# PGTN021_octasource_controls.net
KiCad netlist of a schematic drawn in EAGLE
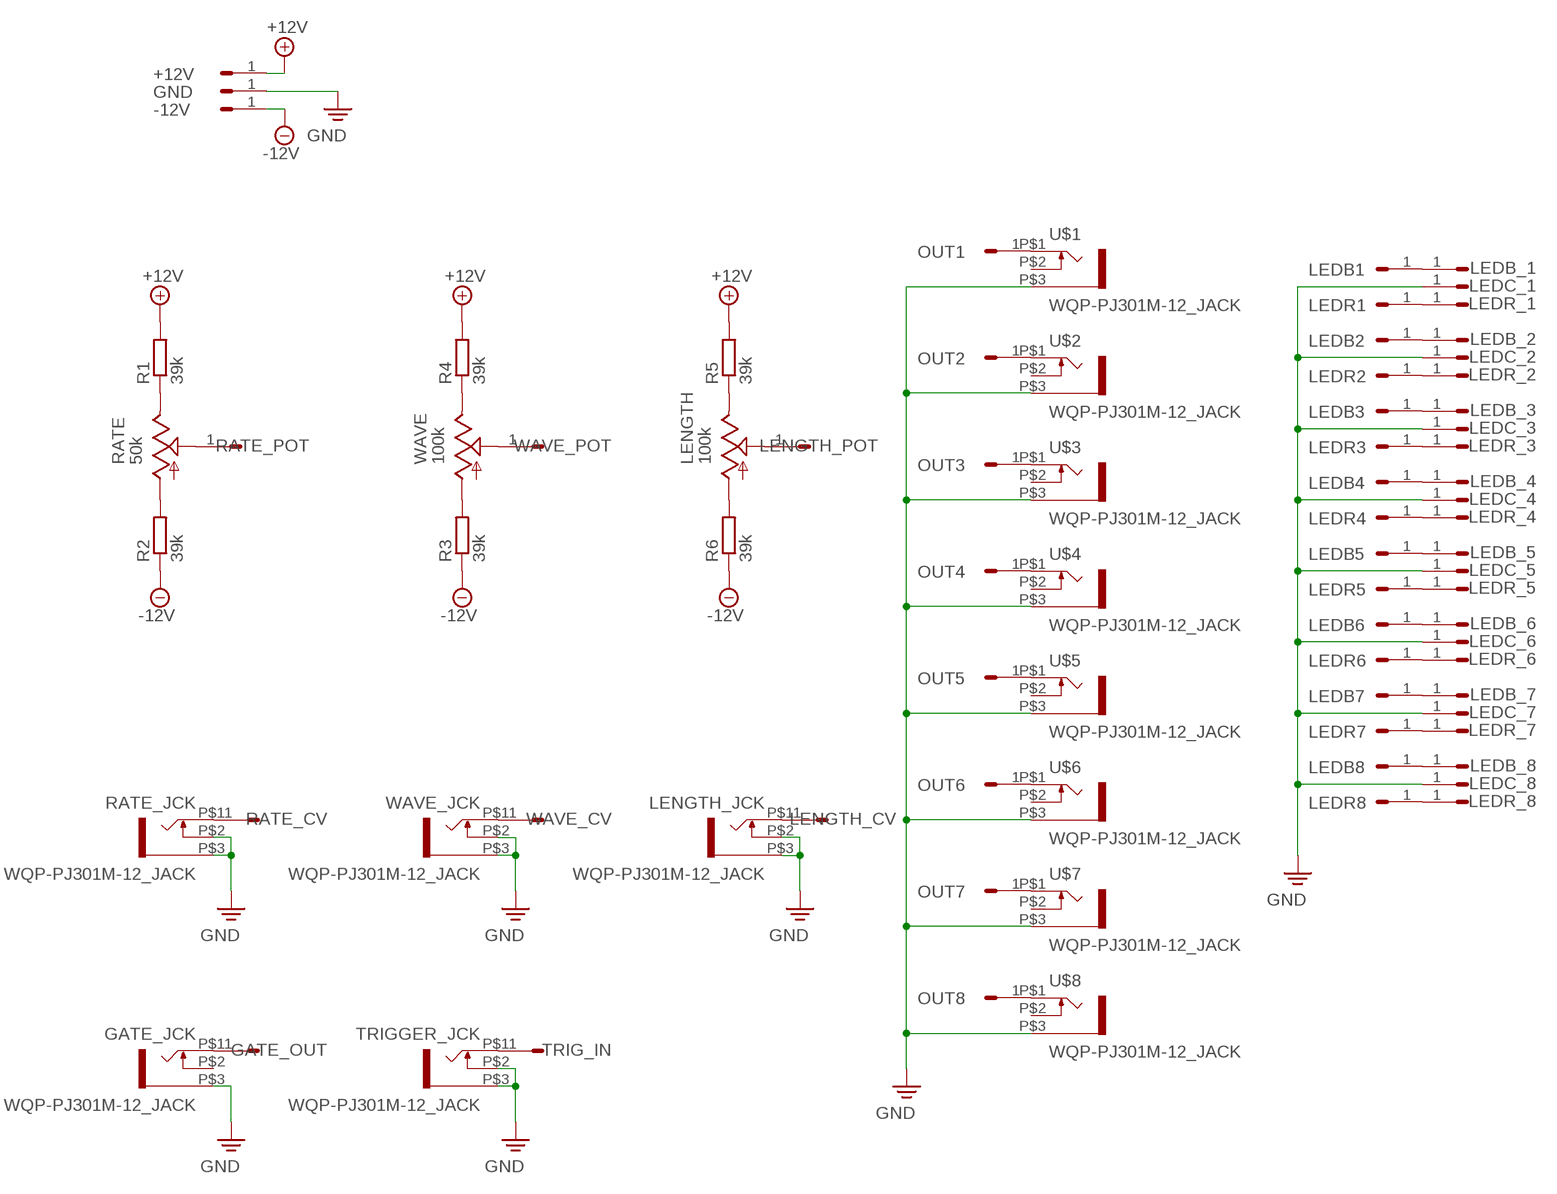
[diagram p0: schematic, sheet 1]

(export (version "E")
  (design (tool "Eeschema 10.0.6"))
  (components
    (comp (ref "+12V")
      (value "HEADER/MALE/01")
      (footprint "eagle-import:HEADER_MALE_01")
      (libsource (lib "eagle-import") (part "HEADER/MALE/01"))
    )
    (comp (ref "-12V")
      (value "HEADER/MALE/01")
      (footprint "eagle-import:HEADER_MALE_01")
      (libsource (lib "eagle-import") (part "HEADER/MALE/01"))
    )
    (comp (ref "GATE_JCK")
      (value "WQP-PJ301M-12_JACK")
      (footprint "eagle-import:WQP-PJ301M-12_JACK")
      (libsource (lib "eagle-import") (part "WQP-PJ301M-12_JACK"))
    )
    (comp (ref "GATE_OUT")
      (value "HEADER/MALE/01")
      (footprint "eagle-import:HEADER_MALE_01")
      (libsource (lib "eagle-import") (part "HEADER/MALE/01"))
    )
    (comp (ref "GND")
      (value "HEADER/MALE/01")
      (footprint "eagle-import:HEADER_MALE_01")
      (libsource (lib "eagle-import") (part "HEADER/MALE/01"))
    )
    (comp (ref "LEDB1")
      (value "HEADER/MALE/01")
      (footprint "eagle-import:HEADER_MALE_01")
      (libsource (lib "eagle-import") (part "HEADER/MALE/01"))
    )
    (comp (ref "LEDB2")
      (value "HEADER/MALE/01")
      (footprint "eagle-import:HEADER_MALE_01")
      (libsource (lib "eagle-import") (part "HEADER/MALE/01"))
    )
    (comp (ref "LEDB3")
      (value "HEADER/MALE/01")
      (footprint "eagle-import:HEADER_MALE_01")
      (libsource (lib "eagle-import") (part "HEADER/MALE/01"))
    )
    (comp (ref "LEDB4")
      (value "HEADER/MALE/01")
      (footprint "eagle-import:HEADER_MALE_01")
      (libsource (lib "eagle-import") (part "HEADER/MALE/01"))
    )
    (comp (ref "LEDB5")
      (value "HEADER/MALE/01")
      (footprint "eagle-import:HEADER_MALE_01")
      (libsource (lib "eagle-import") (part "HEADER/MALE/01"))
    )
    (comp (ref "LEDB6")
      (value "HEADER/MALE/01")
      (footprint "eagle-import:HEADER_MALE_01")
      (libsource (lib "eagle-import") (part "HEADER/MALE/01"))
    )
    (comp (ref "LEDB7")
      (value "HEADER/MALE/01")
      (footprint "eagle-import:HEADER_MALE_01")
      (libsource (lib "eagle-import") (part "HEADER/MALE/01"))
    )
    (comp (ref "LEDB8")
      (value "HEADER/MALE/01")
      (footprint "eagle-import:HEADER_MALE_01")
      (libsource (lib "eagle-import") (part "HEADER/MALE/01"))
    )
    (comp (ref "LEDB_1")
      (value "HEADER/MALE/01")
      (footprint "eagle-import:HEADER_MALE_01")
      (libsource (lib "eagle-import") (part "HEADER/MALE/01"))
    )
    (comp (ref "LEDB_2")
      (value "HEADER/MALE/01")
      (footprint "eagle-import:HEADER_MALE_01")
      (libsource (lib "eagle-import") (part "HEADER/MALE/01"))
    )
    (comp (ref "LEDB_3")
      (value "HEADER/MALE/01")
      (footprint "eagle-import:HEADER_MALE_01")
      (libsource (lib "eagle-import") (part "HEADER/MALE/01"))
    )
    (comp (ref "LEDB_4")
      (value "HEADER/MALE/01")
      (footprint "eagle-import:HEADER_MALE_01")
      (libsource (lib "eagle-import") (part "HEADER/MALE/01"))
    )
    (comp (ref "LEDB_5")
      (value "HEADER/MALE/01")
      (footprint "eagle-import:HEADER_MALE_01")
      (libsource (lib "eagle-import") (part "HEADER/MALE/01"))
    )
    (comp (ref "LEDB_6")
      (value "HEADER/MALE/01")
      (footprint "eagle-import:HEADER_MALE_01")
      (libsource (lib "eagle-import") (part "HEADER/MALE/01"))
    )
    (comp (ref "LEDB_7")
      (value "HEADER/MALE/01")
      (footprint "eagle-import:HEADER_MALE_01")
      (libsource (lib "eagle-import") (part "HEADER/MALE/01"))
    )
    (comp (ref "LEDB_8")
      (value "HEADER/MALE/01")
      (footprint "eagle-import:HEADER_MALE_01")
      (libsource (lib "eagle-import") (part "HEADER/MALE/01"))
    )
    (comp (ref "LEDC_1")
      (value "HEADER/MALE/01")
      (footprint "eagle-import:HEADER_MALE_01")
      (libsource (lib "eagle-import") (part "HEADER/MALE/01"))
    )
    (comp (ref "LEDC_2")
      (value "HEADER/MALE/01")
      (footprint "eagle-import:HEADER_MALE_01")
      (libsource (lib "eagle-import") (part "HEADER/MALE/01"))
    )
    (comp (ref "LEDC_3")
      (value "HEADER/MALE/01")
      (footprint "eagle-import:HEADER_MALE_01")
      (libsource (lib "eagle-import") (part "HEADER/MALE/01"))
    )
    (comp (ref "LEDC_4")
      (value "HEADER/MALE/01")
      (footprint "eagle-import:HEADER_MALE_01")
      (libsource (lib "eagle-import") (part "HEADER/MALE/01"))
    )
    (comp (ref "LEDC_5")
      (value "HEADER/MALE/01")
      (footprint "eagle-import:HEADER_MALE_01")
      (libsource (lib "eagle-import") (part "HEADER/MALE/01"))
    )
    (comp (ref "LEDC_6")
      (value "HEADER/MALE/01")
      (footprint "eagle-import:HEADER_MALE_01")
      (libsource (lib "eagle-import") (part "HEADER/MALE/01"))
    )
    (comp (ref "LEDC_7")
      (value "HEADER/MALE/01")
      (footprint "eagle-import:HEADER_MALE_01")
      (libsource (lib "eagle-import") (part "HEADER/MALE/01"))
    )
    (comp (ref "LEDC_8")
      (value "HEADER/MALE/01")
      (footprint "eagle-import:HEADER_MALE_01")
      (libsource (lib "eagle-import") (part "HEADER/MALE/01"))
    )
    (comp (ref "LEDR1")
      (value "HEADER/MALE/01")
      (footprint "eagle-import:HEADER_MALE_01")
      (libsource (lib "eagle-import") (part "HEADER/MALE/01"))
    )
    (comp (ref "LEDR2")
      (value "HEADER/MALE/01")
      (footprint "eagle-import:HEADER_MALE_01")
      (libsource (lib "eagle-import") (part "HEADER/MALE/01"))
    )
    (comp (ref "LEDR3")
      (value "HEADER/MALE/01")
      (footprint "eagle-import:HEADER_MALE_01")
      (libsource (lib "eagle-import") (part "HEADER/MALE/01"))
    )
    (comp (ref "LEDR4")
      (value "HEADER/MALE/01")
      (footprint "eagle-import:HEADER_MALE_01")
      (libsource (lib "eagle-import") (part "HEADER/MALE/01"))
    )
    (comp (ref "LEDR5")
      (value "HEADER/MALE/01")
      (footprint "eagle-import:HEADER_MALE_01")
      (libsource (lib "eagle-import") (part "HEADER/MALE/01"))
    )
    (comp (ref "LEDR6")
      (value "HEADER/MALE/01")
      (footprint "eagle-import:HEADER_MALE_01")
      (libsource (lib "eagle-import") (part "HEADER/MALE/01"))
    )
    (comp (ref "LEDR7")
      (value "HEADER/MALE/01")
      (footprint "eagle-import:HEADER_MALE_01")
      (libsource (lib "eagle-import") (part "HEADER/MALE/01"))
    )
    (comp (ref "LEDR8")
      (value "HEADER/MALE/01")
      (footprint "eagle-import:HEADER_MALE_01")
      (libsource (lib "eagle-import") (part "HEADER/MALE/01"))
    )
    (comp (ref "LEDR_1")
      (value "HEADER/MALE/01")
      (footprint "eagle-import:HEADER_MALE_01")
      (libsource (lib "eagle-import") (part "HEADER/MALE/01"))
    )
    (comp (ref "LEDR_2")
      (value "HEADER/MALE/01")
      (footprint "eagle-import:HEADER_MALE_01")
      (libsource (lib "eagle-import") (part "HEADER/MALE/01"))
    )
    (comp (ref "LEDR_3")
      (value "HEADER/MALE/01")
      (footprint "eagle-import:HEADER_MALE_01")
      (libsource (lib "eagle-import") (part "HEADER/MALE/01"))
    )
    (comp (ref "LEDR_4")
      (value "HEADER/MALE/01")
      (footprint "eagle-import:HEADER_MALE_01")
      (libsource (lib "eagle-import") (part "HEADER/MALE/01"))
    )
    (comp (ref "LEDR_5")
      (value "HEADER/MALE/01")
      (footprint "eagle-import:HEADER_MALE_01")
      (libsource (lib "eagle-import") (part "HEADER/MALE/01"))
    )
    (comp (ref "LEDR_6")
      (value "HEADER/MALE/01")
      (footprint "eagle-import:HEADER_MALE_01")
      (libsource (lib "eagle-import") (part "HEADER/MALE/01"))
    )
    (comp (ref "LEDR_7")
      (value "HEADER/MALE/01")
      (footprint "eagle-import:HEADER_MALE_01")
      (libsource (lib "eagle-import") (part "HEADER/MALE/01"))
    )
    (comp (ref "LEDR_8")
      (value "HEADER/MALE/01")
      (footprint "eagle-import:HEADER_MALE_01")
      (libsource (lib "eagle-import") (part "HEADER/MALE/01"))
    )
    (comp (ref "LENGTH")
      (value "100k")
      (footprint "eagle-import:9MM_SNAP-IN_POT")
      (libsource (lib "eagle-import") (part "9MM_SNAP-IN_POT_"))
    )
    (comp (ref "LENGTH_CV")
      (value "HEADER/MALE/01")
      (footprint "eagle-import:HEADER_MALE_01")
      (libsource (lib "eagle-import") (part "HEADER/MALE/01"))
    )
    (comp (ref "LENGTH_JCK")
      (value "WQP-PJ301M-12_JACK")
      (footprint "eagle-import:WQP-PJ301M-12_JACK")
      (libsource (lib "eagle-import") (part "WQP-PJ301M-12_JACK"))
    )
    (comp (ref "LENGTH_POT")
      (value "HEADER/MALE/01")
      (footprint "eagle-import:HEADER_MALE_01")
      (libsource (lib "eagle-import") (part "HEADER/MALE/01"))
    )
    (comp (ref "OUT1")
      (value "HEADER/MALE/01")
      (footprint "eagle-import:HEADER_MALE_01")
      (libsource (lib "eagle-import") (part "HEADER/MALE/01"))
    )
    (comp (ref "OUT2")
      (value "HEADER/MALE/01")
      (footprint "eagle-import:HEADER_MALE_01")
      (libsource (lib "eagle-import") (part "HEADER/MALE/01"))
    )
    (comp (ref "OUT3")
      (value "HEADER/MALE/01")
      (footprint "eagle-import:HEADER_MALE_01")
      (libsource (lib "eagle-import") (part "HEADER/MALE/01"))
    )
    (comp (ref "OUT4")
      (value "HEADER/MALE/01")
      (footprint "eagle-import:HEADER_MALE_01")
      (libsource (lib "eagle-import") (part "HEADER/MALE/01"))
    )
    (comp (ref "OUT5")
      (value "HEADER/MALE/01")
      (footprint "eagle-import:HEADER_MALE_01")
      (libsource (lib "eagle-import") (part "HEADER/MALE/01"))
    )
    (comp (ref "OUT6")
      (value "HEADER/MALE/01")
      (footprint "eagle-import:HEADER_MALE_01")
      (libsource (lib "eagle-import") (part "HEADER/MALE/01"))
    )
    (comp (ref "OUT7")
      (value "HEADER/MALE/01")
      (footprint "eagle-import:HEADER_MALE_01")
      (libsource (lib "eagle-import") (part "HEADER/MALE/01"))
    )
    (comp (ref "OUT8")
      (value "HEADER/MALE/01")
      (footprint "eagle-import:HEADER_MALE_01")
      (libsource (lib "eagle-import") (part "HEADER/MALE/01"))
    )
    (comp (ref "R1")
      (value "39k")
      (footprint "eagle-import:RESISTOR_7.5")
      (libsource (lib "eagle-import") (part "RESISTORRESISTOR/UPRIGHT/7.5"))
    )
    (comp (ref "R2")
      (value "39k")
      (footprint "eagle-import:RESISTOR_7.5")
      (libsource (lib "eagle-import") (part "RESISTORRESISTOR/UPRIGHT/7.5"))
    )
    (comp (ref "R3")
      (value "39k")
      (footprint "eagle-import:RESISTOR_7.5")
      (libsource (lib "eagle-import") (part "RESISTORRESISTOR/UPRIGHT/7.5"))
    )
    (comp (ref "R4")
      (value "39k")
      (footprint "eagle-import:RESISTOR_7.5")
      (libsource (lib "eagle-import") (part "RESISTORRESISTOR/UPRIGHT/7.5"))
    )
    (comp (ref "R5")
      (value "39k")
      (footprint "eagle-import:RESISTOR_7.5")
      (libsource (lib "eagle-import") (part "RESISTORRESISTOR/UPRIGHT/7.5"))
    )
    (comp (ref "R6")
      (value "39k")
      (footprint "eagle-import:RESISTOR_7.5")
      (libsource (lib "eagle-import") (part "RESISTORRESISTOR/UPRIGHT/7.5"))
    )
    (comp (ref "RATE")
      (value "50k")
      (footprint "eagle-import:9MM_SNAP-IN_POT")
      (libsource (lib "eagle-import") (part "9MM_SNAP-IN_POT_"))
    )
    (comp (ref "RATE_CV")
      (value "HEADER/MALE/01")
      (footprint "eagle-import:HEADER_MALE_01")
      (libsource (lib "eagle-import") (part "HEADER/MALE/01"))
    )
    (comp (ref "RATE_JCK")
      (value "WQP-PJ301M-12_JACK")
      (footprint "eagle-import:WQP-PJ301M-12_JACK")
      (libsource (lib "eagle-import") (part "WQP-PJ301M-12_JACK"))
    )
    (comp (ref "RATE_POT")
      (value "HEADER/MALE/01")
      (footprint "eagle-import:HEADER_MALE_01")
      (libsource (lib "eagle-import") (part "HEADER/MALE/01"))
    )
    (comp (ref "TRIGGER_JCK")
      (value "WQP-PJ301M-12_JACK")
      (footprint "eagle-import:WQP-PJ301M-12_JACK")
      (libsource (lib "eagle-import") (part "WQP-PJ301M-12_JACK"))
    )
    (comp (ref "TRIG_IN")
      (value "HEADER/MALE/01")
      (footprint "eagle-import:HEADER_MALE_01")
      (libsource (lib "eagle-import") (part "HEADER/MALE/01"))
    )
    (comp (ref "U$1")
      (value "WQP-PJ301M-12_JACK")
      (footprint "eagle-import:WQP-PJ301M-12_JACK")
      (libsource (lib "eagle-import") (part "WQP-PJ301M-12_JACK"))
    )
    (comp (ref "U$2")
      (value "WQP-PJ301M-12_JACK")
      (footprint "eagle-import:WQP-PJ301M-12_JACK")
      (libsource (lib "eagle-import") (part "WQP-PJ301M-12_JACK"))
    )
    (comp (ref "U$3")
      (value "WQP-PJ301M-12_JACK")
      (footprint "eagle-import:WQP-PJ301M-12_JACK")
      (libsource (lib "eagle-import") (part "WQP-PJ301M-12_JACK"))
    )
    (comp (ref "U$4")
      (value "WQP-PJ301M-12_JACK")
      (footprint "eagle-import:WQP-PJ301M-12_JACK")
      (libsource (lib "eagle-import") (part "WQP-PJ301M-12_JACK"))
    )
    (comp (ref "U$5")
      (value "WQP-PJ301M-12_JACK")
      (footprint "eagle-import:WQP-PJ301M-12_JACK")
      (libsource (lib "eagle-import") (part "WQP-PJ301M-12_JACK"))
    )
    (comp (ref "U$6")
      (value "WQP-PJ301M-12_JACK")
      (footprint "eagle-import:WQP-PJ301M-12_JACK")
      (libsource (lib "eagle-import") (part "WQP-PJ301M-12_JACK"))
    )
    (comp (ref "U$7")
      (value "WQP-PJ301M-12_JACK")
      (footprint "eagle-import:WQP-PJ301M-12_JACK")
      (libsource (lib "eagle-import") (part "WQP-PJ301M-12_JACK"))
    )
    (comp (ref "U$8")
      (value "WQP-PJ301M-12_JACK")
      (footprint "eagle-import:WQP-PJ301M-12_JACK")
      (libsource (lib "eagle-import") (part "WQP-PJ301M-12_JACK"))
    )
    (comp (ref "WAVE")
      (value "100k")
      (footprint "eagle-import:9MM_SNAP-IN_POT")
      (libsource (lib "eagle-import") (part "9MM_SNAP-IN_POT_"))
    )
    (comp (ref "WAVE_CV")
      (value "HEADER/MALE/01")
      (footprint "eagle-import:HEADER_MALE_01")
      (libsource (lib "eagle-import") (part "HEADER/MALE/01"))
    )
    (comp (ref "WAVE_JCK")
      (value "WQP-PJ301M-12_JACK")
      (footprint "eagle-import:WQP-PJ301M-12_JACK")
      (libsource (lib "eagle-import") (part "WQP-PJ301M-12_JACK"))
    )
    (comp (ref "WAVE_POT")
      (value "HEADER/MALE/01")
      (footprint "eagle-import:HEADER_MALE_01")
      (libsource (lib "eagle-import") (part "HEADER/MALE/01"))
    )
  )
  (nets
    (net (code "1") (name "+12V") (class "Default")
      (node (ref "+12V") (pin "1") (pinfunction "3_1") (pintype "passive"))
      (node (ref "R1") (pin "2") (pinfunction "2_2") (pintype "passive"))
      (node (ref "R4") (pin "2") (pinfunction "2_2") (pintype "passive"))
      (node (ref "R5") (pin "2") (pinfunction "2_2") (pintype "passive"))
    )
    (net (code "2") (name "-12V") (class "Default")
      (node (ref "-12V") (pin "1") (pinfunction "3_1") (pintype "passive"))
      (node (ref "R2") (pin "1") (pinfunction "1_1") (pintype "passive"))
      (node (ref "R3") (pin "1") (pinfunction "1_1") (pintype "passive"))
      (node (ref "R6") (pin "1") (pinfunction "1_1") (pintype "passive"))
    )
    (net (code "3") (name "GND") (class "Default")
      (node (ref "GATE_JCK") (pin "P$3") (pinfunction "1_P$3") (pintype "passive"))
      (node (ref "GND") (pin "1") (pinfunction "3_1") (pintype "passive"))
      (node (ref "LEDC_1") (pin "1") (pinfunction "3_1") (pintype "passive"))
      (node (ref "LEDC_2") (pin "1") (pinfunction "3_1") (pintype "passive"))
      (node (ref "LEDC_3") (pin "1") (pinfunction "3_1") (pintype "passive"))
      (node (ref "LEDC_4") (pin "1") (pinfunction "3_1") (pintype "passive"))
      (node (ref "LEDC_5") (pin "1") (pinfunction "3_1") (pintype "passive"))
      (node (ref "LEDC_6") (pin "1") (pinfunction "3_1") (pintype "passive"))
      (node (ref "LEDC_7") (pin "1") (pinfunction "3_1") (pintype "passive"))
      (node (ref "LEDC_8") (pin "1") (pinfunction "3_1") (pintype "passive"))
      (node (ref "LENGTH_JCK") (pin "P$2") (pinfunction "3_P$2") (pintype "passive"))
      (node (ref "LENGTH_JCK") (pin "P$3") (pinfunction "1_P$3") (pintype "passive"))
      (node (ref "RATE_JCK") (pin "P$2") (pinfunction "3_P$2") (pintype "passive"))
      (node (ref "RATE_JCK") (pin "P$3") (pinfunction "1_P$3") (pintype "passive"))
      (node (ref "TRIGGER_JCK") (pin "P$2") (pinfunction "3_P$2") (pintype "passive"))
      (node (ref "TRIGGER_JCK") (pin "P$3") (pinfunction "1_P$3") (pintype "passive"))
      (node (ref "U$1") (pin "P$3") (pinfunction "1_P$3") (pintype "passive"))
      (node (ref "U$2") (pin "P$3") (pinfunction "1_P$3") (pintype "passive"))
      (node (ref "U$3") (pin "P$3") (pinfunction "1_P$3") (pintype "passive"))
      (node (ref "U$4") (pin "P$3") (pinfunction "1_P$3") (pintype "passive"))
      (node (ref "U$5") (pin "P$3") (pinfunction "1_P$3") (pintype "passive"))
      (node (ref "U$6") (pin "P$3") (pinfunction "1_P$3") (pintype "passive"))
      (node (ref "U$7") (pin "P$3") (pinfunction "1_P$3") (pintype "passive"))
      (node (ref "U$8") (pin "P$3") (pinfunction "1_P$3") (pintype "passive"))
      (node (ref "WAVE_JCK") (pin "P$2") (pinfunction "3_P$2") (pintype "passive"))
      (node (ref "WAVE_JCK") (pin "P$3") (pinfunction "1_P$3") (pintype "passive"))
    )
    (net (code "4") (name "Net-(GATE_JCK-2)") (class "Default")
      (node (ref "GATE_JCK") (pin "P$1") (pinfunction "2_P$1") (pintype "passive"))
      (node (ref "GATE_OUT") (pin "1") (pinfunction "3_1") (pintype "passive"))
    )
    (net (code "5") (name "Net-(LEDB1-3)") (class "Default")
      (node (ref "LEDB1") (pin "1") (pinfunction "3_1") (pintype "passive"))
      (node (ref "LEDB_1") (pin "1") (pinfunction "3_1") (pintype "passive"))
    )
    (net (code "6") (name "Net-(LEDB2-3)") (class "Default")
      (node (ref "LEDB2") (pin "1") (pinfunction "3_1") (pintype "passive"))
      (node (ref "LEDB_2") (pin "1") (pinfunction "3_1") (pintype "passive"))
    )
    (net (code "7") (name "Net-(LEDB3-3)") (class "Default")
      (node (ref "LEDB3") (pin "1") (pinfunction "3_1") (pintype "passive"))
      (node (ref "LEDB_3") (pin "1") (pinfunction "3_1") (pintype "passive"))
    )
    (net (code "8") (name "Net-(LEDB4-3)") (class "Default")
      (node (ref "LEDB4") (pin "1") (pinfunction "3_1") (pintype "passive"))
      (node (ref "LEDB_4") (pin "1") (pinfunction "3_1") (pintype "passive"))
    )
    (net (code "9") (name "Net-(LEDB5-3)") (class "Default")
      (node (ref "LEDB5") (pin "1") (pinfunction "3_1") (pintype "passive"))
      (node (ref "LEDB_5") (pin "1") (pinfunction "3_1") (pintype "passive"))
    )
    (net (code "10") (name "Net-(LEDB6-3)") (class "Default")
      (node (ref "LEDB6") (pin "1") (pinfunction "3_1") (pintype "passive"))
      (node (ref "LEDB_6") (pin "1") (pinfunction "3_1") (pintype "passive"))
    )
    (net (code "11") (name "Net-(LEDB7-3)") (class "Default")
      (node (ref "LEDB7") (pin "1") (pinfunction "3_1") (pintype "passive"))
      (node (ref "LEDB_7") (pin "1") (pinfunction "3_1") (pintype "passive"))
    )
    (net (code "12") (name "Net-(LEDB8-3)") (class "Default")
      (node (ref "LEDB8") (pin "1") (pinfunction "3_1") (pintype "passive"))
      (node (ref "LEDB_8") (pin "1") (pinfunction "3_1") (pintype "passive"))
    )
    (net (code "13") (name "Net-(LEDR1-3)") (class "Default")
      (node (ref "LEDR1") (pin "1") (pinfunction "3_1") (pintype "passive"))
      (node (ref "LEDR_1") (pin "1") (pinfunction "3_1") (pintype "passive"))
    )
    (net (code "14") (name "Net-(LEDR2-3)") (class "Default")
      (node (ref "LEDR2") (pin "1") (pinfunction "3_1") (pintype "passive"))
      (node (ref "LEDR_2") (pin "1") (pinfunction "3_1") (pintype "passive"))
    )
    (net (code "15") (name "Net-(LEDR3-3)") (class "Default")
      (node (ref "LEDR3") (pin "1") (pinfunction "3_1") (pintype "passive"))
      (node (ref "LEDR_3") (pin "1") (pinfunction "3_1") (pintype "passive"))
    )
    (net (code "16") (name "Net-(LEDR4-3)") (class "Default")
      (node (ref "LEDR4") (pin "1") (pinfunction "3_1") (pintype "passive"))
      (node (ref "LEDR_4") (pin "1") (pinfunction "3_1") (pintype "passive"))
    )
    (net (code "17") (name "Net-(LEDR5-3)") (class "Default")
      (node (ref "LEDR5") (pin "1") (pinfunction "3_1") (pintype "passive"))
      (node (ref "LEDR_5") (pin "1") (pinfunction "3_1") (pintype "passive"))
    )
    (net (code "18") (name "Net-(LEDR6-3)") (class "Default")
      (node (ref "LEDR6") (pin "1") (pinfunction "3_1") (pintype "passive"))
      (node (ref "LEDR_6") (pin "1") (pinfunction "3_1") (pintype "passive"))
    )
    (net (code "19") (name "Net-(LEDR7-3)") (class "Default")
      (node (ref "LEDR7") (pin "1") (pinfunction "3_1") (pintype "passive"))
      (node (ref "LEDR_7") (pin "1") (pinfunction "3_1") (pintype "passive"))
    )
    (net (code "20") (name "Net-(LEDR8-3)") (class "Default")
      (node (ref "LEDR8") (pin "1") (pinfunction "3_1") (pintype "passive"))
      (node (ref "LEDR_8") (pin "1") (pinfunction "3_1") (pintype "passive"))
    )
    (net (code "21") (name "Net-(LENGTH-A)") (class "Default")
      (node (ref "LENGTH") (pin "1") (pinfunction "A_1") (pintype "passive"))
      (node (ref "R6") (pin "2") (pinfunction "2_2") (pintype "passive"))
    )
    (net (code "22") (name "Net-(LENGTH-E)") (class "Default")
      (node (ref "LENGTH") (pin "3") (pinfunction "E_3") (pintype "passive"))
      (node (ref "R5") (pin "1") (pinfunction "1_1") (pintype "passive"))
    )
    (net (code "23") (name "Net-(LENGTH-S)") (class "Default")
      (node (ref "LENGTH") (pin "2") (pinfunction "S_2") (pintype "passive"))
      (node (ref "LENGTH_POT") (pin "1") (pinfunction "3_1") (pintype "passive"))
    )
    (net (code "24") (name "Net-(LENGTH_CV-3)") (class "Default")
      (node (ref "LENGTH_CV") (pin "1") (pinfunction "3_1") (pintype "passive"))
      (node (ref "LENGTH_JCK") (pin "P$1") (pinfunction "2_P$1") (pintype "passive"))
    )
    (net (code "25") (name "Net-(OUT1-3)") (class "Default")
      (node (ref "OUT1") (pin "1") (pinfunction "3_1") (pintype "passive"))
      (node (ref "U$1") (pin "P$1") (pinfunction "2_P$1") (pintype "passive"))
    )
    (net (code "26") (name "Net-(OUT2-3)") (class "Default")
      (node (ref "OUT2") (pin "1") (pinfunction "3_1") (pintype "passive"))
      (node (ref "U$2") (pin "P$1") (pinfunction "2_P$1") (pintype "passive"))
    )
    (net (code "27") (name "Net-(OUT3-3)") (class "Default")
      (node (ref "OUT3") (pin "1") (pinfunction "3_1") (pintype "passive"))
      (node (ref "U$3") (pin "P$1") (pinfunction "2_P$1") (pintype "passive"))
    )
    (net (code "28") (name "Net-(OUT4-3)") (class "Default")
      (node (ref "OUT4") (pin "1") (pinfunction "3_1") (pintype "passive"))
      (node (ref "U$4") (pin "P$1") (pinfunction "2_P$1") (pintype "passive"))
    )
    (net (code "29") (name "Net-(OUT5-3)") (class "Default")
      (node (ref "OUT5") (pin "1") (pinfunction "3_1") (pintype "passive"))
      (node (ref "U$5") (pin "P$1") (pinfunction "2_P$1") (pintype "passive"))
    )
    (net (code "30") (name "Net-(OUT6-3)") (class "Default")
      (node (ref "OUT6") (pin "1") (pinfunction "3_1") (pintype "passive"))
      (node (ref "U$6") (pin "P$1") (pinfunction "2_P$1") (pintype "passive"))
    )
    (net (code "31") (name "Net-(OUT7-3)") (class "Default")
      (node (ref "OUT7") (pin "1") (pinfunction "3_1") (pintype "passive"))
      (node (ref "U$7") (pin "P$1") (pinfunction "2_P$1") (pintype "passive"))
    )
    (net (code "32") (name "Net-(OUT8-3)") (class "Default")
      (node (ref "OUT8") (pin "1") (pinfunction "3_1") (pintype "passive"))
      (node (ref "U$8") (pin "P$1") (pinfunction "2_P$1") (pintype "passive"))
    )
    (net (code "33") (name "Net-(RATE-A)") (class "Default")
      (node (ref "R2") (pin "2") (pinfunction "2_2") (pintype "passive"))
      (node (ref "RATE") (pin "1") (pinfunction "A_1") (pintype "passive"))
    )
    (net (code "34") (name "Net-(RATE-E)") (class "Default")
      (node (ref "R1") (pin "1") (pinfunction "1_1") (pintype "passive"))
      (node (ref "RATE") (pin "3") (pinfunction "E_3") (pintype "passive"))
    )
    (net (code "35") (name "Net-(RATE-S)") (class "Default")
      (node (ref "RATE") (pin "2") (pinfunction "S_2") (pintype "passive"))
      (node (ref "RATE_POT") (pin "1") (pinfunction "3_1") (pintype "passive"))
    )
    (net (code "36") (name "Net-(RATE_CV-3)") (class "Default")
      (node (ref "RATE_CV") (pin "1") (pinfunction "3_1") (pintype "passive"))
      (node (ref "RATE_JCK") (pin "P$1") (pinfunction "2_P$1") (pintype "passive"))
    )
    (net (code "37") (name "Net-(TRIGGER_JCK-2)") (class "Default")
      (node (ref "TRIGGER_JCK") (pin "P$1") (pinfunction "2_P$1") (pintype "passive"))
      (node (ref "TRIG_IN") (pin "1") (pinfunction "3_1") (pintype "passive"))
    )
    (net (code "38") (name "Net-(WAVE-A)") (class "Default")
      (node (ref "R3") (pin "2") (pinfunction "2_2") (pintype "passive"))
      (node (ref "WAVE") (pin "1") (pinfunction "A_1") (pintype "passive"))
    )
    (net (code "39") (name "Net-(WAVE-E)") (class "Default")
      (node (ref "R4") (pin "1") (pinfunction "1_1") (pintype "passive"))
      (node (ref "WAVE") (pin "3") (pinfunction "E_3") (pintype "passive"))
    )
    (net (code "40") (name "Net-(WAVE-S)") (class "Default")
      (node (ref "WAVE") (pin "2") (pinfunction "S_2") (pintype "passive"))
      (node (ref "WAVE_POT") (pin "1") (pinfunction "3_1") (pintype "passive"))
    )
    (net (code "41") (name "Net-(WAVE_CV-3)") (class "Default")
      (node (ref "WAVE_CV") (pin "1") (pinfunction "3_1") (pintype "passive"))
      (node (ref "WAVE_JCK") (pin "P$1") (pinfunction "2_P$1") (pintype "passive"))
    )
    (net (code "42") (name "unconnected-(GATE_JCK-3-PadP$2)") (class "Default")
      (node (ref "GATE_JCK") (pin "P$2") (pinfunction "3_P$2") (pintype "passive"))
    )
    (net (code "43") (name "unconnected-(U$1-3-PadP$2)") (class "Default")
      (node (ref "U$1") (pin "P$2") (pinfunction "3_P$2") (pintype "passive"))
    )
    (net (code "44") (name "unconnected-(U$2-3-PadP$2)") (class "Default")
      (node (ref "U$2") (pin "P$2") (pinfunction "3_P$2") (pintype "passive"))
    )
    (net (code "45") (name "unconnected-(U$3-3-PadP$2)") (class "Default")
      (node (ref "U$3") (pin "P$2") (pinfunction "3_P$2") (pintype "passive"))
    )
    (net (code "46") (name "unconnected-(U$4-3-PadP$2)") (class "Default")
      (node (ref "U$4") (pin "P$2") (pinfunction "3_P$2") (pintype "passive"))
    )
    (net (code "47") (name "unconnected-(U$5-3-PadP$2)") (class "Default")
      (node (ref "U$5") (pin "P$2") (pinfunction "3_P$2") (pintype "passive"))
    )
    (net (code "48") (name "unconnected-(U$6-3-PadP$2)") (class "Default")
      (node (ref "U$6") (pin "P$2") (pinfunction "3_P$2") (pintype "passive"))
    )
    (net (code "49") (name "unconnected-(U$7-3-PadP$2)") (class "Default")
      (node (ref "U$7") (pin "P$2") (pinfunction "3_P$2") (pintype "passive"))
    )
    (net (code "50") (name "unconnected-(U$8-3-PadP$2)") (class "Default")
      (node (ref "U$8") (pin "P$2") (pinfunction "3_P$2") (pintype "passive"))
    )
  )
)
